# CutDown2_V1_0.net
KiCad netlist of a schematic drawn in EAGLE
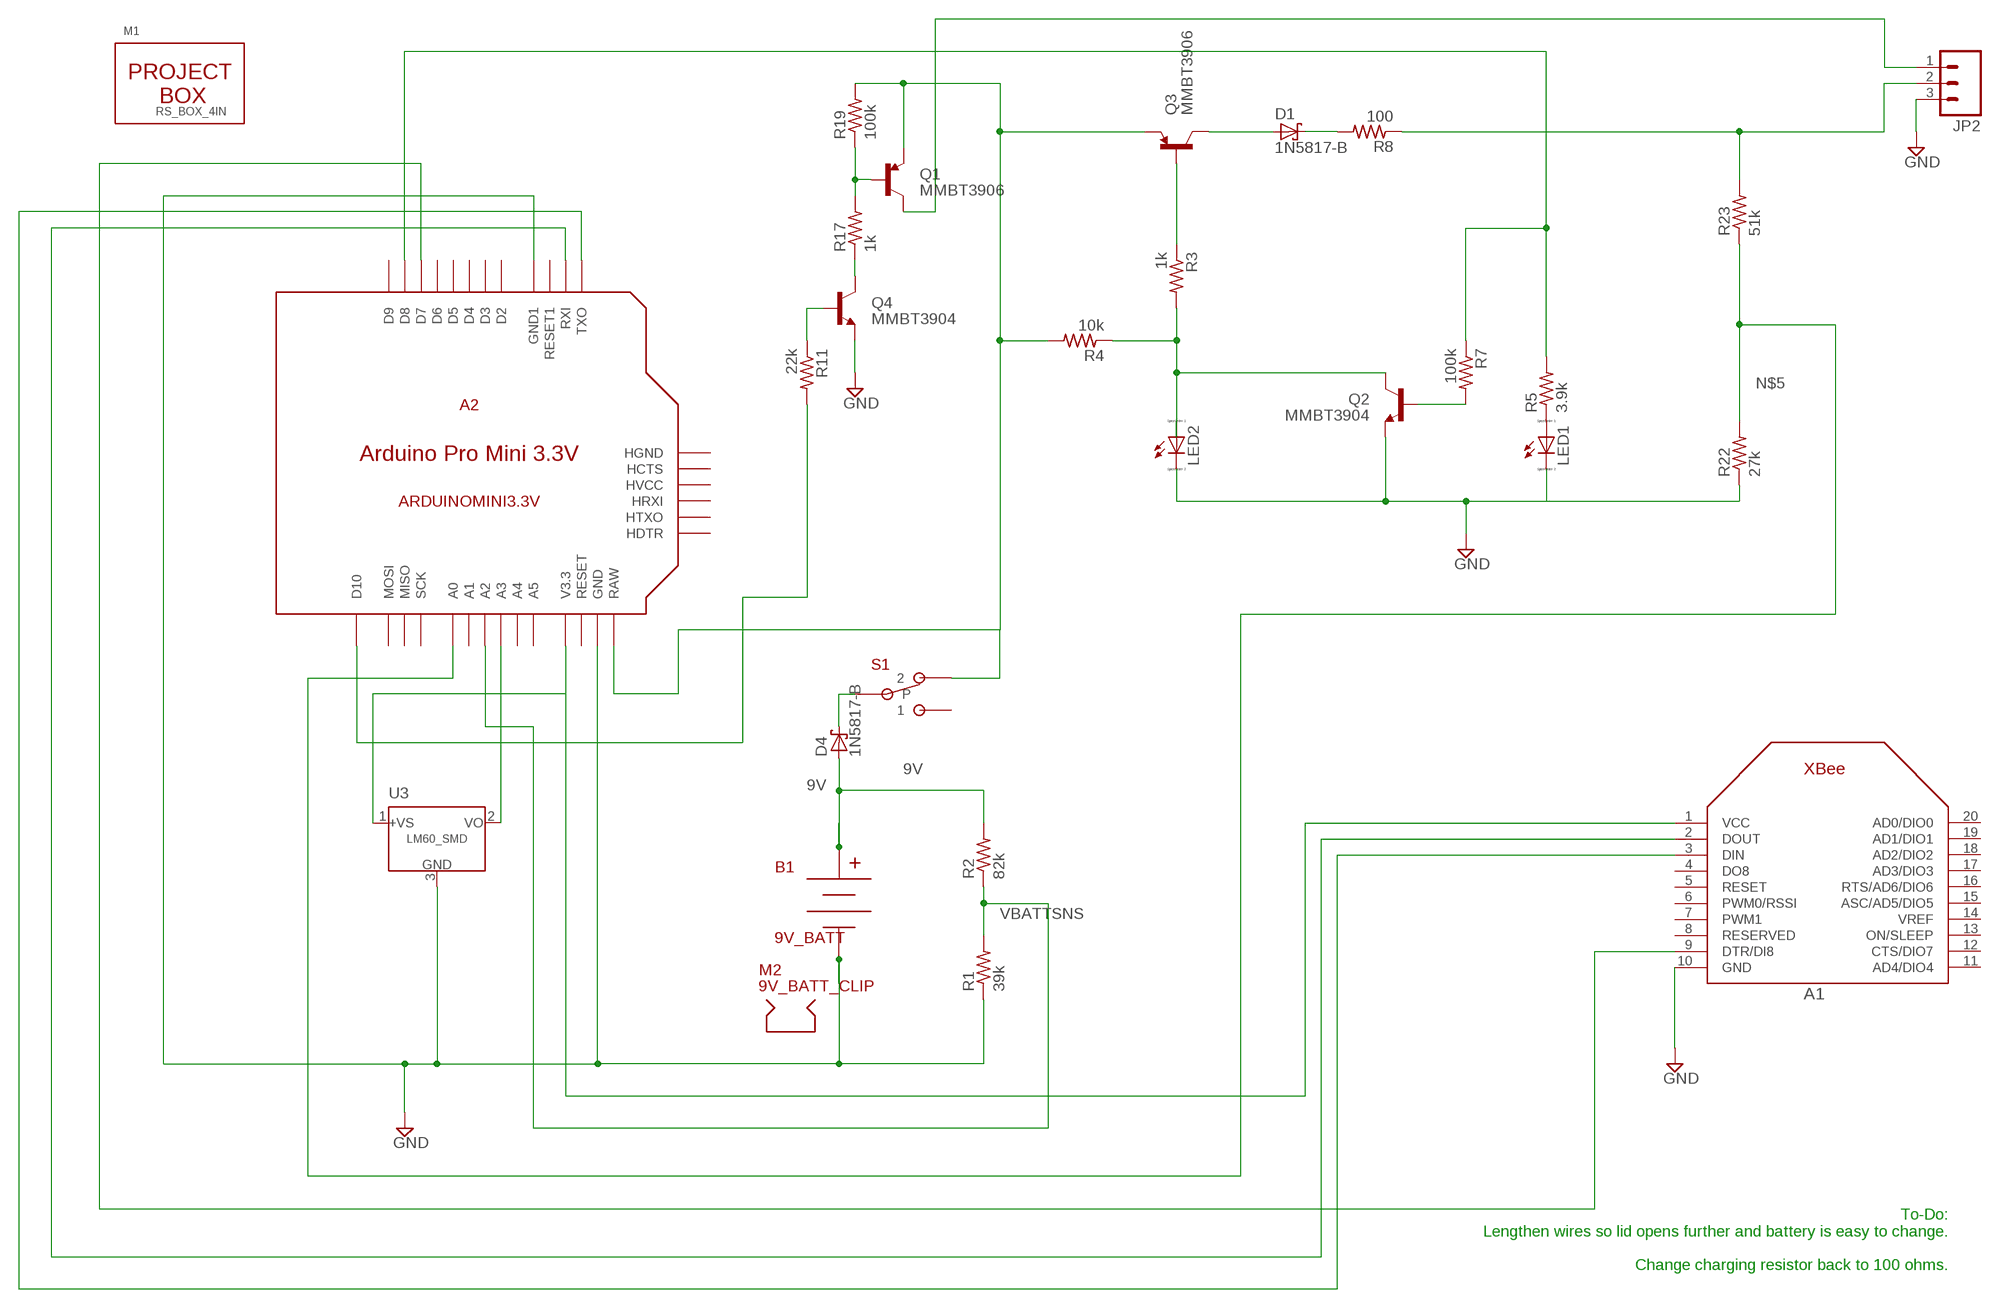
[diagram p0: schematic, sheet 1]

(export (version "E")
  (design (tool "Eeschema 10.0.6"))
  (components
    (comp (ref "A1")
      (value "XBEE")
      (footprint "eagle-import:XBEE")
      (libsource (lib "eagle-import") (part "XBEE"))
    )
    (comp (ref "A2")
      (value "ARDUINOMINI3.3V")
      (footprint "eagle-import:ARDUINOMINI3.3V")
      (libsource (lib "eagle-import") (part "ARDUINOMINI3.3V"))
    )
    (comp (ref "B1")
      (value "9V_BATT")
      (footprint "eagle-import:KEYSTONE_593_594")
      (libsource (lib "eagle-import") (part "9V_BATT"))
    )
    (comp (ref "D1")
      (value "1N5817-B")
      (footprint "eagle-import:DO41-7.6")
      (libsource (lib "eagle-import") (part "1N5817-B"))
    )
    (comp (ref "D4")
      (value "1N5817-B")
      (footprint "eagle-import:DO41-7.6")
      (libsource (lib "eagle-import") (part "1N5817-B"))
    )
    (comp (ref "JP2")
      (value "M03POLAR_LOCK")
      (footprint "eagle-import:MOLEX-1X3_LOCK")
      (libsource (lib "eagle-import") (part "M03POLAR_LOCK"))
    )
    (comp (ref "LED1")
      (value "LED_ELD260")
      (footprint "eagle-import:LED_LD260")
      (libsource (lib "eagle-import") (part "LED_ELD260"))
    )
    (comp (ref "LED2")
      (value "LED_ELD260")
      (footprint "eagle-import:LED_LD260")
      (libsource (lib "eagle-import") (part "LED_ELD260"))
    )
    (comp (ref "M1")
      (value "RS_BOX_4IN")
      (footprint "eagle-import:RS_BOX_OUTLINE_4IN")
      (libsource (lib "eagle-import") (part "RS_BOX_4IN"))
    )
    (comp (ref "M2")
      (value "9V_BATT_CLIP")
      (footprint "eagle-import:KEYSTONE_9V_CLIP_H")
      (libsource (lib "eagle-import") (part "9V_BATT_CLIP"))
    )
    (comp (ref "Q1")
      (value "MMBT3906")
      (footprint "eagle-import:SOT23")
      (libsource (lib "eagle-import") (part "TRANSISTOR_PNPMMBT4403"))
    )
    (comp (ref "Q2")
      (value "MMBT3904")
      (footprint "eagle-import:SOT23")
      (libsource (lib "eagle-import") (part "TRANSISTOR_NPNSOT23"))
    )
    (comp (ref "Q3")
      (value "MMBT3906")
      (footprint "eagle-import:SOT23")
      (libsource (lib "eagle-import") (part "TRANSISTOR_PNPMMBT4403"))
    )
    (comp (ref "Q4")
      (value "MMBT3904")
      (footprint "eagle-import:SOT23")
      (libsource (lib "eagle-import") (part "TRANSISTOR_NPNSOT23"))
    )
    (comp (ref "R1")
      (value "39k")
      (footprint "eagle-import:R0805")
      (libsource (lib "eagle-import") (part "R-US_R0805"))
    )
    (comp (ref "R2")
      (value "82k")
      (footprint "eagle-import:R0805")
      (libsource (lib "eagle-import") (part "R-US_R0805"))
    )
    (comp (ref "R3")
      (value "1k")
      (footprint "eagle-import:R0805")
      (libsource (lib "eagle-import") (part "R-US_R0805"))
    )
    (comp (ref "R4")
      (value "10k")
      (footprint "eagle-import:R0805")
      (libsource (lib "eagle-import") (part "R-US_R0805"))
    )
    (comp (ref "R5")
      (value "3.9k")
      (footprint "eagle-import:R0805")
      (libsource (lib "eagle-import") (part "R-US_R0805"))
    )
    (comp (ref "R7")
      (value "100k")
      (footprint "eagle-import:R0805")
      (libsource (lib "eagle-import") (part "R-US_R0805"))
    )
    (comp (ref "R8")
      (value "100")
      (footprint "eagle-import:R0805")
      (libsource (lib "eagle-import") (part "R-US_R0805"))
    )
    (comp (ref "R11")
      (value "22k")
      (footprint "eagle-import:R0805")
      (libsource (lib "eagle-import") (part "R-US_R0805"))
    )
    (comp (ref "R17")
      (value "1k")
      (footprint "eagle-import:R0805")
      (libsource (lib "eagle-import") (part "R-US_R0805"))
    )
    (comp (ref "R19")
      (value "100k")
      (footprint "eagle-import:R0805")
      (libsource (lib "eagle-import") (part "R-US_R0805"))
    )
    (comp (ref "R22")
      (value "27k")
      (footprint "eagle-import:R0805")
      (libsource (lib "eagle-import") (part "R-US_R0805"))
    )
    (comp (ref "R23")
      (value "51k")
      (footprint "eagle-import:R0805")
      (libsource (lib "eagle-import") (part "R-US_R0805"))
    )
    (comp (ref "S1")
      (value "APEM_SPDT_25000NH")
      (footprint "eagle-import:APEM_SPDT_25000NH")
      (libsource (lib "eagle-import") (part "APEM_SPDT_25000NH"))
    )
    (comp (ref "U3")
      (value "LM60_SMD")
      (footprint "eagle-import:SOT23-3")
      (libsource (lib "eagle-import") (part "LM60_SMD"))
    )
  )
  (nets
    (net (code "1") (name "/9V") (class "Default")
      (node (ref "B1") (pin "P$1") (pinfunction "V+_P$1") (pintype "bidirectional"))
      (node (ref "B1") (pin "P$2") (pinfunction "V+_P$2") (pintype "bidirectional"))
      (node (ref "B1") (pin "P$3") (pinfunction "V+_P$3") (pintype "bidirectional"))
      (node (ref "D4") (pin "A") (pinfunction "A_A") (pintype "passive"))
      (node (ref "R2") (pin "2") (pinfunction "2_2") (pintype "passive"))
    )
    (net (code "2") (name "/N$5") (class "Default")
      (node (ref "A2") (pin "P$26") (pinfunction "A0_P$26") (pintype "bidirectional"))
      (node (ref "R22") (pin "2") (pinfunction "2_2") (pintype "passive"))
      (node (ref "R23") (pin "1") (pinfunction "1_1") (pintype "passive"))
    )
    (net (code "3") (name "/VBATTSNS") (class "Default")
      (node (ref "A2") (pin "P$24") (pinfunction "A2_P$24") (pintype "bidirectional"))
      (node (ref "R1") (pin "2") (pinfunction "2_2") (pintype "passive"))
      (node (ref "R2") (pin "1") (pinfunction "1_1") (pintype "passive"))
    )
    (net (code "4") (name "GND") (class "Default")
      (node (ref "A1") (pin "10") (pinfunction "GND_10") (pintype "power_in"))
      (node (ref "A2") (pin "P$20") (pinfunction "GND_P$20") (pintype "power_in"))
      (node (ref "A2") (pin "P$9") (pinfunction "GND1_P$9") (pintype "bidirectional"))
      (node (ref "B1") (pin "P$4") (pinfunction "V-_P$4") (pintype "bidirectional"))
      (node (ref "B1") (pin "P$5") (pinfunction "V-_P$5") (pintype "bidirectional"))
      (node (ref "B1") (pin "P$6") (pinfunction "V-_P$6") (pintype "bidirectional"))
      (node (ref "JP2") (pin "3") (pinfunction "3_3") (pintype "passive"))
      (node (ref "LED1") (pin "K") (pinfunction "C_K") (pintype "passive"))
      (node (ref "LED2") (pin "K") (pinfunction "C_K") (pintype "passive"))
      (node (ref "Q2") (pin "2") (pinfunction "E_2") (pintype "passive"))
      (node (ref "Q4") (pin "2") (pinfunction "E_2") (pintype "passive"))
      (node (ref "R1") (pin "1") (pinfunction "1_1") (pintype "passive"))
      (node (ref "R22") (pin "1") (pinfunction "1_1") (pintype "passive"))
      (node (ref "U3") (pin "3") (pinfunction "GND_3") (pintype "power_in"))
    )
    (net (code "5") (name "Net-(A1-DIN)") (class "Default")
      (node (ref "A1") (pin "3") (pinfunction "DIN_3") (pintype "input"))
      (node (ref "A2") (pin "P$12") (pinfunction "TXO_P$12") (pintype "bidirectional"))
    )
    (net (code "6") (name "Net-(A1-DOUT)") (class "Default")
      (node (ref "A1") (pin "2") (pinfunction "DOUT_2") (pintype "output"))
      (node (ref "A2") (pin "P$11") (pinfunction "RXI_P$11") (pintype "bidirectional"))
    )
    (net (code "7") (name "Net-(A1-DTR{slash}DI8)") (class "Default")
      (node (ref "A1") (pin "9") (pinfunction "DTR/DI8_9") (pintype "input"))
      (node (ref "A2") (pin "P$3") (pinfunction "D7_P$3") (pintype "bidirectional"))
    )
    (net (code "8") (name "Net-(A1-VCC)") (class "Default")
      (node (ref "A1") (pin "1") (pinfunction "VCC_1") (pintype "power_in"))
      (node (ref "A2") (pin "P$22") (pinfunction "V3.3_P$22") (pintype "power_in"))
      (node (ref "U3") (pin "1") (pinfunction "+VS_1") (pintype "input"))
    )
    (net (code "9") (name "Net-(A2-A3)") (class "Default")
      (node (ref "A2") (pin "P$23") (pinfunction "A3_P$23") (pintype "bidirectional"))
      (node (ref "U3") (pin "2") (pinfunction "VO_2") (pintype "input"))
    )
    (net (code "10") (name "Net-(A2-D8)") (class "Default")
      (node (ref "A2") (pin "P$2") (pinfunction "D8_P$2") (pintype "bidirectional"))
      (node (ref "R5") (pin "2") (pinfunction "2_2") (pintype "passive"))
      (node (ref "R7") (pin "1") (pinfunction "1_1") (pintype "passive"))
    )
    (net (code "11") (name "Net-(A2-D10)") (class "Default")
      (node (ref "A2") (pin "P$30") (pinfunction "D10_P$30") (pintype "bidirectional"))
      (node (ref "R11") (pin "2") (pinfunction "2_2") (pintype "passive"))
    )
    (net (code "12") (name "Net-(A2-RAW)") (class "Default")
      (node (ref "A2") (pin "P$19") (pinfunction "RAW_P$19") (pintype "bidirectional"))
      (node (ref "Q1") (pin "2") (pinfunction "E_2") (pintype "passive"))
      (node (ref "Q3") (pin "2") (pinfunction "E_2") (pintype "passive"))
      (node (ref "R19") (pin "2") (pinfunction "2_2") (pintype "passive"))
      (node (ref "R4") (pin "2") (pinfunction "2_2") (pintype "passive"))
      (node (ref "S1") (pin "P$2") (pinfunction "2_P$2") (pintype "bidirectional"))
    )
    (net (code "13") (name "Net-(D1-PadC)") (class "Default")
      (node (ref "D1") (pin "C") (pinfunction "C_C") (pintype "passive"))
      (node (ref "R8") (pin "2") (pinfunction "2_2") (pintype "passive"))
    )
    (net (code "14") (name "Net-(JP2-Pad2)") (class "Default")
      (node (ref "JP2") (pin "2") (pinfunction "2_2") (pintype "passive"))
      (node (ref "R23") (pin "2") (pinfunction "2_2") (pintype "passive"))
      (node (ref "R8") (pin "1") (pinfunction "1_1") (pintype "passive"))
    )
    (net (code "15") (name "Net-(LED1-PadA)") (class "Default")
      (node (ref "LED1") (pin "A") (pinfunction "A_A") (pintype "passive"))
      (node (ref "R5") (pin "1") (pinfunction "1_1") (pintype "passive"))
    )
    (net (code "16") (name "Net-(Q1-B)") (class "Default")
      (node (ref "Q1") (pin "1") (pinfunction "B_1") (pintype "passive"))
      (node (ref "R17") (pin "2") (pinfunction "2_2") (pintype "passive"))
      (node (ref "R19") (pin "1") (pinfunction "1_1") (pintype "passive"))
    )
    (net (code "17") (name "Net-(Q1-C)") (class "Default")
      (node (ref "JP2") (pin "1") (pinfunction "1_1") (pintype "passive"))
      (node (ref "Q1") (pin "3") (pinfunction "C_3") (pintype "passive"))
    )
    (net (code "18") (name "Net-(Q2-B)") (class "Default")
      (node (ref "Q2") (pin "1") (pinfunction "B_1") (pintype "passive"))
      (node (ref "R7") (pin "2") (pinfunction "2_2") (pintype "passive"))
    )
    (net (code "19") (name "Net-(Q2-C)") (class "Default")
      (node (ref "LED2") (pin "A") (pinfunction "A_A") (pintype "passive"))
      (node (ref "Q2") (pin "3") (pinfunction "C_3") (pintype "passive"))
      (node (ref "R3") (pin "2") (pinfunction "2_2") (pintype "passive"))
      (node (ref "R4") (pin "1") (pinfunction "1_1") (pintype "passive"))
    )
    (net (code "20") (name "Net-(Q3-B)") (class "Default")
      (node (ref "Q3") (pin "1") (pinfunction "B_1") (pintype "passive"))
      (node (ref "R3") (pin "1") (pinfunction "1_1") (pintype "passive"))
    )
    (net (code "21") (name "Net-(Q3-C)") (class "Default")
      (node (ref "D1") (pin "A") (pinfunction "A_A") (pintype "passive"))
      (node (ref "Q3") (pin "3") (pinfunction "C_3") (pintype "passive"))
    )
    (net (code "22") (name "Net-(Q4-B)") (class "Default")
      (node (ref "Q4") (pin "1") (pinfunction "B_1") (pintype "passive"))
      (node (ref "R11") (pin "1") (pinfunction "1_1") (pintype "passive"))
    )
    (net (code "23") (name "Net-(Q4-C)") (class "Default")
      (node (ref "Q4") (pin "3") (pinfunction "C_3") (pintype "passive"))
      (node (ref "R17") (pin "1") (pinfunction "1_1") (pintype "passive"))
    )
    (net (code "24") (name "Net-(S1-P)") (class "Default")
      (node (ref "D4") (pin "C") (pinfunction "C_C") (pintype "passive"))
      (node (ref "S1") (pin "P$3") (pinfunction "P_P$3") (pintype "bidirectional"))
    )
    (net (code "25") (name "unconnected-(A1-AD0{slash}DIO0-Pad20)") (class "Default")
      (node (ref "A1") (pin "20") (pinfunction "AD0/DIO0_20") (pintype "bidirectional"))
    )
    (net (code "26") (name "unconnected-(A1-AD1{slash}DIO1-Pad19)") (class "Default")
      (node (ref "A1") (pin "19") (pinfunction "AD1/DIO1_19") (pintype "bidirectional"))
    )
    (net (code "27") (name "unconnected-(A1-AD2{slash}DIO2-Pad18)") (class "Default")
      (node (ref "A1") (pin "18") (pinfunction "AD2/DIO2_18") (pintype "bidirectional"))
    )
    (net (code "28") (name "unconnected-(A1-AD3{slash}DIO3-Pad17)") (class "Default")
      (node (ref "A1") (pin "17") (pinfunction "AD3/DIO3_17") (pintype "bidirectional"))
    )
    (net (code "29") (name "unconnected-(A1-AD4{slash}DIO4-Pad11)") (class "Default")
      (node (ref "A1") (pin "11") (pinfunction "AD4/DIO4_11") (pintype "bidirectional"))
    )
    (net (code "30") (name "unconnected-(A1-ASC{slash}AD5{slash}DIO5-Pad15)") (class "Default")
      (node (ref "A1") (pin "15") (pinfunction "ASC/AD5/DIO5_15") (pintype "bidirectional"))
    )
    (net (code "31") (name "unconnected-(A1-CTS{slash}DIO7-Pad12)") (class "Default")
      (node (ref "A1") (pin "12") (pinfunction "CTS/DIO7_12") (pintype "bidirectional"))
    )
    (net (code "32") (name "unconnected-(A1-DO8-Pad4)") (class "Default")
      (node (ref "A1") (pin "4") (pinfunction "DO8_4") (pintype "output"))
    )
    (net (code "33") (name "unconnected-(A1-ON{slash}SLEEP-Pad13)") (class "Default")
      (node (ref "A1") (pin "13") (pinfunction "ON/SLEEP_13") (pintype "output"))
    )
    (net (code "34") (name "unconnected-(A1-PWM0{slash}RSSI-Pad6)") (class "Default")
      (node (ref "A1") (pin "6") (pinfunction "PWM0/RSSI_6") (pintype "output"))
    )
    (net (code "35") (name "unconnected-(A1-PWM1-Pad7)") (class "Default")
      (node (ref "A1") (pin "7") (pinfunction "PWM1_7") (pintype "output"))
    )
    (net (code "36") (name "unconnected-(A1-RESERVED-Pad8)") (class "Default")
      (node (ref "A1") (pin "8") (pinfunction "RESERVED_8") (pintype "no_connect"))
    )
    (net (code "37") (name "unconnected-(A1-RESET-Pad5)") (class "Default")
      (node (ref "A1") (pin "5") (pinfunction "RESET_5") (pintype "input"))
    )
    (net (code "38") (name "unconnected-(A1-RTS{slash}AD6{slash}DIO6-Pad16)") (class "Default")
      (node (ref "A1") (pin "16") (pinfunction "RTS/AD6/DIO6_16") (pintype "bidirectional"))
    )
    (net (code "39") (name "unconnected-(A1-VREF-Pad14)") (class "Default")
      (node (ref "A1") (pin "14") (pinfunction "VREF_14") (pintype "input"))
    )
    (net (code "40") (name "unconnected-(A2-A1-PadP$25)") (class "Default")
      (node (ref "A2") (pin "P$25") (pinfunction "A1_P$25") (pintype "bidirectional"))
    )
    (net (code "41") (name "unconnected-(A2-A4-PadP$35)") (class "Default")
      (node (ref "A2") (pin "P$35") (pinfunction "A4_P$35") (pintype "bidirectional"))
    )
    (net (code "42") (name "unconnected-(A2-A5-PadP$34)") (class "Default")
      (node (ref "A2") (pin "P$34") (pinfunction "A5_P$34") (pintype "bidirectional"))
    )
    (net (code "43") (name "unconnected-(A2-D2-PadP$8)") (class "Default")
      (node (ref "A2") (pin "P$8") (pinfunction "D2_P$8") (pintype "bidirectional"))
    )
    (net (code "44") (name "unconnected-(A2-D3-PadP$7)") (class "Default")
      (node (ref "A2") (pin "P$7") (pinfunction "D3_P$7") (pintype "bidirectional"))
    )
    (net (code "45") (name "unconnected-(A2-D4-PadP$6)") (class "Default")
      (node (ref "A2") (pin "P$6") (pinfunction "D4_P$6") (pintype "bidirectional"))
    )
    (net (code "46") (name "unconnected-(A2-D5-PadP$5)") (class "Default")
      (node (ref "A2") (pin "P$5") (pinfunction "D5_P$5") (pintype "bidirectional"))
    )
    (net (code "47") (name "unconnected-(A2-D6-PadP$4)") (class "Default")
      (node (ref "A2") (pin "P$4") (pinfunction "D6_P$4") (pintype "bidirectional"))
    )
    (net (code "48") (name "unconnected-(A2-D9-PadP$1)") (class "Default")
      (node (ref "A2") (pin "P$1") (pinfunction "D9_P$1") (pintype "bidirectional"))
    )
    (net (code "49") (name "unconnected-(A2-HCTS-PadP$14)") (class "Default")
      (node (ref "A2") (pin "P$14") (pinfunction "HCTS_P$14") (pintype "bidirectional"))
    )
    (net (code "50") (name "unconnected-(A2-HDTR-PadP$18)") (class "Default")
      (node (ref "A2") (pin "P$18") (pinfunction "HDTR_P$18") (pintype "bidirectional"))
    )
    (net (code "51") (name "unconnected-(A2-HGND-PadP$13)") (class "Default")
      (node (ref "A2") (pin "P$13") (pinfunction "HGND_P$13") (pintype "bidirectional"))
    )
    (net (code "52") (name "unconnected-(A2-HRXI-PadP$16)") (class "Default")
      (node (ref "A2") (pin "P$16") (pinfunction "HRXI_P$16") (pintype "bidirectional"))
    )
    (net (code "53") (name "unconnected-(A2-HTXO-PadP$17)") (class "Default")
      (node (ref "A2") (pin "P$17") (pinfunction "HTXO_P$17") (pintype "bidirectional"))
    )
    (net (code "54") (name "unconnected-(A2-HVCC-PadP$15)") (class "Default")
      (node (ref "A2") (pin "P$15") (pinfunction "HVCC_P$15") (pintype "bidirectional"))
    )
    (net (code "55") (name "unconnected-(A2-MISO-PadP$28)") (class "Default")
      (node (ref "A2") (pin "P$28") (pinfunction "MISO_P$28") (pintype "bidirectional"))
    )
    (net (code "56") (name "unconnected-(A2-MOSI-PadP$29)") (class "Default")
      (node (ref "A2") (pin "P$29") (pinfunction "MOSI_P$29") (pintype "bidirectional"))
    )
    (net (code "57") (name "unconnected-(A2-RESET-PadP$21)") (class "Default")
      (node (ref "A2") (pin "P$21") (pinfunction "RESET_P$21") (pintype "bidirectional"))
    )
    (net (code "58") (name "unconnected-(A2-RESET1-PadP$10)") (class "Default")
      (node (ref "A2") (pin "P$10") (pinfunction "RESET1_P$10") (pintype "bidirectional"))
    )
    (net (code "59") (name "unconnected-(A2-SCK-PadP$27)") (class "Default")
      (node (ref "A2") (pin "P$27") (pinfunction "SCK_P$27") (pintype "bidirectional"))
    )
    (net (code "60") (name "unconnected-(S1-1-PadP$1)") (class "Default")
      (node (ref "S1") (pin "P$1") (pinfunction "1_P$1") (pintype "bidirectional"))
    )
  )
)
